# CONNECTORS.net
KiCad netlist of a schematic drawn in Altium Designer
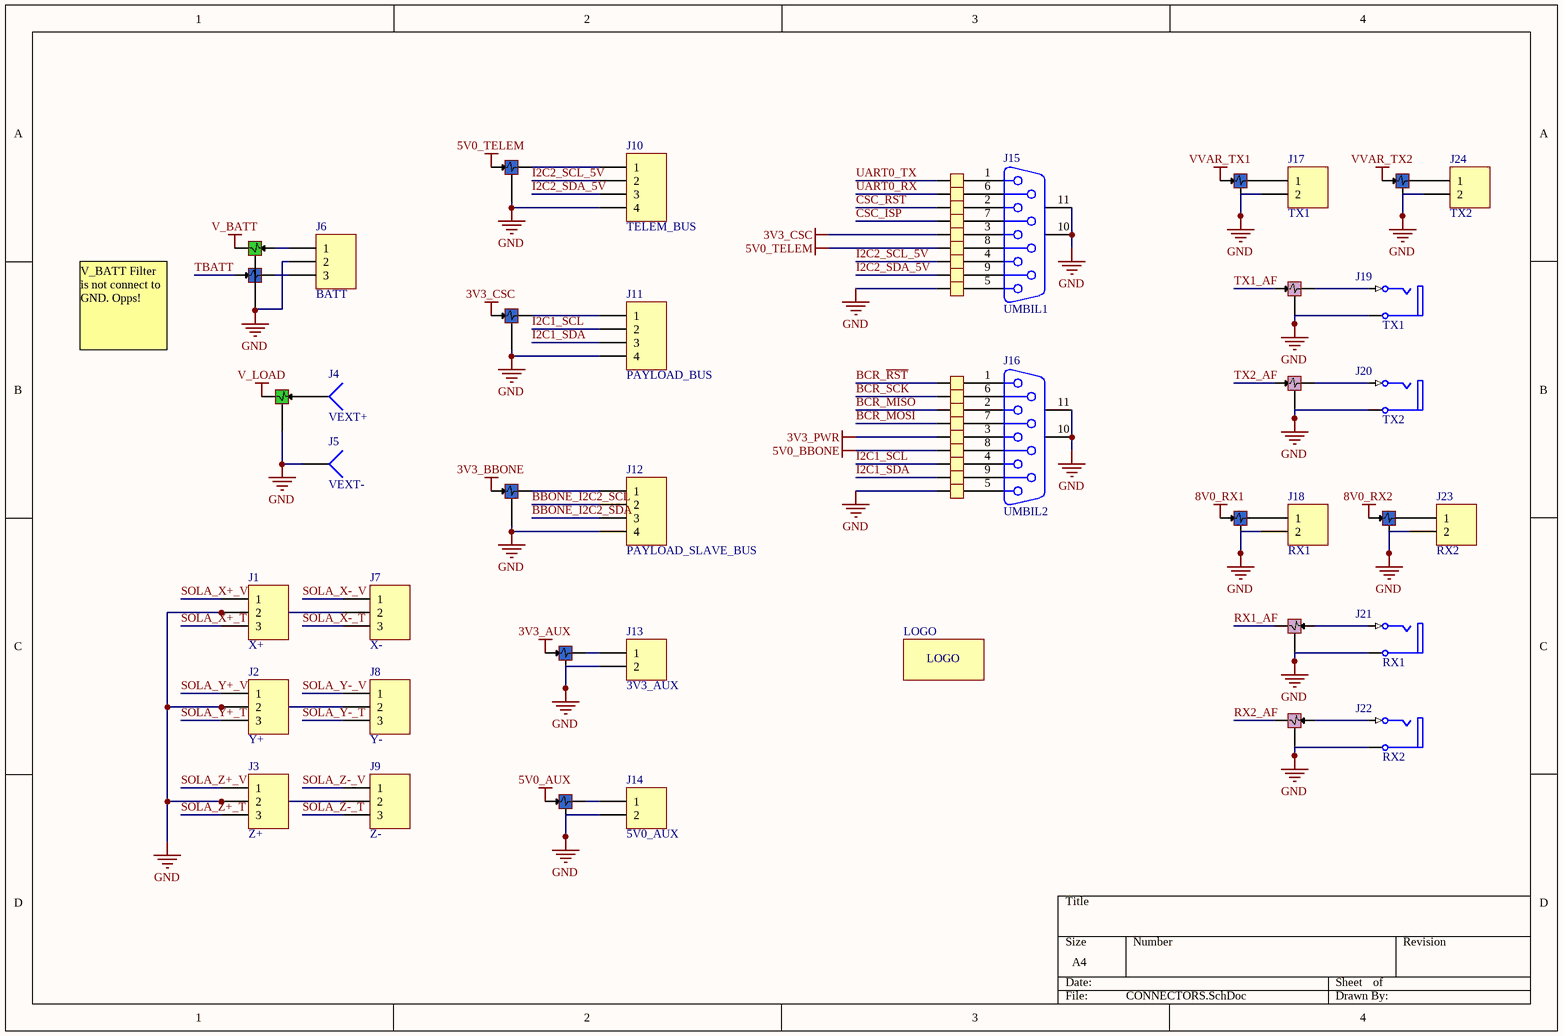
[diagram p0: CONNECTORS.SchDoc]

(export (version "E")
  (design (tool "Eeschema 10.0.6"))
  (components
    (comp (ref "F1")
      (value "FilterSola")
      (footprint "FILTERSOLA")
      (libsource (lib "FlatBoards") (part "FilterSola"))
    )
    (comp (ref "F2")
      (value "FilterPwr")
      (footprint "FILTERPWR")
      (libsource (lib "FlatBoards") (part "FilterPwr"))
    )
    (comp (ref "F3")
      (value "FilterPwr")
      (footprint "FILTERPWR")
      (libsource (lib "FlatBoards") (part "FilterPwr"))
    )
    (comp (ref "F4")
      (value "FilterPwr")
      (footprint "FILTERPWR")
      (libsource (lib "FlatBoards") (part "FilterPwr"))
    )
    (comp (ref "F5")
      (value "FilterPwr")
      (footprint "FILTERPWR")
      (libsource (lib "FlatBoards") (part "FilterPwr"))
    )
    (comp (ref "F6")
      (value "FilterPwr")
      (footprint "FILTERPWR")
      (libsource (lib "FlatBoards") (part "FilterPwr"))
    )
    (comp (ref "F7")
      (value "FilterPwr")
      (footprint "FILTERPWR")
      (libsource (lib "FlatBoards") (part "FilterPwr"))
    )
    (comp (ref "F8")
      (value "FilterPwr")
      (footprint "FILTERPWR")
      (libsource (lib "FlatBoards") (part "FilterPwr"))
    )
    (comp (ref "F9") (value "Filter") (footprint "Filter") (libsource (lib "") (part "Filter_1")))
    (comp (ref "F10") (value "Filter") (footprint "Filter") (libsource (lib "") (part "Filter_1")))
    (comp (ref "F11") (value "Filter") (footprint "Filter") (libsource (lib "FlatBoards") (part "Filter")))
    (comp (ref "F12") (value "Filter") (footprint "Filter") (libsource (lib "FlatBoards") (part "Filter")))
    (comp (ref "F13")
      (value "FilterPwr")
      (footprint "FILTERPWR")
      (libsource (lib "FlatBoards") (part "FilterPwr"))
    )
    (comp (ref "F14")
      (value "FilterPwr")
      (footprint "FILTERPWR")
      (libsource (lib "FlatBoards") (part "FilterPwr"))
    )
    (comp (ref "F98")
      (value "FilterPwr")
      (footprint "FILTERPWR")
      (libsource (lib "FlatBoards") (part "FilterPwr"))
    )
    (comp (ref "F99")
      (value "FilterSola")
      (footprint "FILTERSOLA")
      (libsource (lib "FlatBoards") (part "FilterSola"))
    )
    (comp (ref "J1")
      (value "X+")
      (footprint "SCREW3")
      (description "Header, 3-Pin")
      (fields (field (name "PUBLISHER") "Altium Limited"))
      (libsource (lib "Miscellaneous Connectors") (part "Header 3"))
    )
    (comp (ref "J2")
      (value "Y+")
      (footprint "SCREW3")
      (description "Header, 3-Pin")
      (fields (field (name "PUBLISHER") "Altium Limited"))
      (libsource (lib "Miscellaneous Connectors") (part "Header 3"))
    )
    (comp (ref "J3")
      (value "Z+")
      (footprint "SCREW3")
      (description "Header, 3-Pin")
      (fields (field (name "PUBLISHER") "Altium Limited"))
      (libsource (lib "Miscellaneous Connectors") (part "Header 3"))
    )
    (comp (ref "J4")
      (value "VEXT+")
      (footprint "4MM_BANANA")
      (description "Socket")
      (fields (field (name "PUBLISHER") "Altium Limited"))
      (libsource (lib "Miscellaneous Connectors") (part "Socket"))
    )
    (comp (ref "J5")
      (value "VEXT-")
      (footprint "4MM_BANANA")
      (description "Socket")
      (fields (field (name "PUBLISHER") "Altium Limited"))
      (libsource (lib "Miscellaneous Connectors") (part "Socket"))
    )
    (comp (ref "J6")
      (value "BATT")
      (footprint "SCREW3")
      (description "Header, 3-Pin")
      (fields (field (name "PUBLISHER") "Altium Limited"))
      (libsource (lib "Miscellaneous Connectors") (part "Header 3"))
    )
    (comp (ref "J7")
      (value "X-")
      (footprint "SCREW3")
      (description "Header, 3-Pin")
      (fields (field (name "PUBLISHER") "Altium Limited"))
      (libsource (lib "Miscellaneous Connectors") (part "Header 3"))
    )
    (comp (ref "J8")
      (value "Y-")
      (footprint "SCREW3")
      (description "Header, 3-Pin")
      (fields (field (name "PUBLISHER") "Altium Limited"))
      (libsource (lib "Miscellaneous Connectors") (part "Header 3"))
    )
    (comp (ref "J9")
      (value "Z-")
      (footprint "SCREW3")
      (description "Header, 3-Pin")
      (fields (field (name "PUBLISHER") "Altium Limited"))
      (libsource (lib "Miscellaneous Connectors") (part "Header 3"))
    )
    (comp (ref "J10")
      (value "TELEM_BUS")
      (footprint "HDR1X4")
      (description "Header, 4-Pin")
      (fields (field (name "PUBLISHER") "Altium Limited"))
      (libsource (lib "Miscellaneous Connectors") (part "Header 4"))
    )
    (comp (ref "J11")
      (value "PAYLOAD_BUS")
      (footprint "HDR1X4")
      (description "Header, 4-Pin")
      (fields (field (name "PUBLISHER") "Altium Limited"))
      (libsource (lib "Miscellaneous Connectors") (part "Header 4"))
    )
    (comp (ref "J12")
      (value "PAYLOAD_SLAVE_BUS")
      (footprint "HDR1X4")
      (description "Header, 4-Pin")
      (fields (field (name "PUBLISHER") "Altium Limited"))
      (libsource (lib "Miscellaneous Connectors") (part "Header 4"))
    )
    (comp (ref "J13")
      (value "3V3_AUX")
      (footprint "SCREW2")
      (description "Header, 2-Pin")
      (fields (field (name "PUBLISHER") "Altium Limited"))
      (libsource (lib "Miscellaneous Connectors") (part "Header 2"))
    )
    (comp (ref "J14")
      (value "5V0_AUX")
      (footprint "SCREW2")
      (description "Header, 2-Pin")
      (fields (field (name "PUBLISHER") "Altium Limited"))
      (libsource (lib "Miscellaneous Connectors") (part "Header 2"))
    )
    (comp (ref "J15")
      (value "UMBIL1")
      (footprint "D9 - temp")
      (description "Receptacle Assembly, 9 Position, Right Angle")
      (fields (field (name "PUBLISHER") "Altium Limited"))
      (libsource (lib "Miscellaneous Connectors") (part "D Connector 9"))
    )
    (comp (ref "J16")
      (value "UMBIL2")
      (footprint "D9 - temp")
      (description "Receptacle Assembly, 9 Position, Right Angle")
      (fields (field (name "PUBLISHER") "Altium Limited"))
      (libsource (lib "Miscellaneous Connectors") (part "D Connector 9"))
    )
    (comp (ref "J17")
      (value "TX1")
      (footprint "SCREW2")
      (description "Header, 2-Pin")
      (fields (field (name "PUBLISHER") "Altium Limited"))
      (libsource (lib "Miscellaneous Connectors") (part "Header 2"))
    )
    (comp (ref "J18")
      (value "RX1")
      (footprint "SCREW2")
      (description "Header, 2-Pin")
      (fields (field (name "PUBLISHER") "Altium Limited"))
      (libsource (lib "Miscellaneous Connectors") (part "Header 2"))
    )
    (comp (ref "J19")
      (value "TX1")
      (footprint "R/A RCA")
      (description "RCA Phono Jack, Right Angle, Thru-Hole, Snap-In")
      (fields (field (name "PUBLISHER") "Altium Limited"))
      (libsource (lib "Miscellaneous Connectors") (part "RCA"))
    )
    (comp (ref "J20")
      (value "TX2")
      (footprint "R/A RCA")
      (description "RCA Phono Jack, Right Angle, Thru-Hole, Snap-In")
      (fields (field (name "PUBLISHER") "Altium Limited"))
      (libsource (lib "Miscellaneous Connectors") (part "RCA"))
    )
    (comp (ref "J21")
      (value "RX1")
      (footprint "R/A RCA")
      (description "RCA Phono Jack, Right Angle, Thru-Hole, Snap-In")
      (fields (field (name "PUBLISHER") "Altium Limited"))
      (libsource (lib "Miscellaneous Connectors") (part "RCA"))
    )
    (comp (ref "J22")
      (value "RX2")
      (footprint "R/A RCA")
      (description "RCA Phono Jack, Right Angle, Thru-Hole, Snap-In")
      (fields (field (name "PUBLISHER") "Altium Limited"))
      (libsource (lib "Miscellaneous Connectors") (part "RCA"))
    )
    (comp (ref "J23")
      (value "RX2")
      (footprint "SCREW2")
      (description "Header, 2-Pin")
      (fields (field (name "PUBLISHER") "Altium Limited"))
      (libsource (lib "Miscellaneous Connectors") (part "Header 2"))
    )
    (comp (ref "J24")
      (value "TX2")
      (footprint "SCREW2")
      (description "Header, 2-Pin")
      (fields (field (name "PUBLISHER") "Altium Limited"))
      (libsource (lib "Miscellaneous Connectors") (part "Header 2"))
    )
    (comp (ref "LOGO") (value "~") (footprint "LOGO") (libsource (lib "FlatBoards") (part "LOGO")))
    (comp (ref "P185") (value "Jumper") (footprint "Jumper") (libsource (lib "FlatBoards") (part "Jumper")))
    (comp (ref "P186") (value "Jumper") (footprint "Jumper") (libsource (lib "FlatBoards") (part "Jumper")))
    (comp (ref "P187") (value "Jumper") (footprint "Jumper") (libsource (lib "FlatBoards") (part "Jumper")))
    (comp (ref "P188") (value "Jumper") (footprint "Jumper") (libsource (lib "FlatBoards") (part "Jumper")))
    (comp (ref "P189") (value "Jumper") (footprint "Jumper") (libsource (lib "FlatBoards") (part "Jumper")))
    (comp (ref "P190") (value "Jumper") (footprint "Jumper") (libsource (lib "FlatBoards") (part "Jumper")))
    (comp (ref "P191") (value "Jumper") (footprint "Jumper") (libsource (lib "FlatBoards") (part "Jumper")))
    (comp (ref "P192") (value "Jumper") (footprint "Jumper") (libsource (lib "FlatBoards") (part "Jumper")))
    (comp (ref "P193") (value "Jumper") (footprint "Jumper") (libsource (lib "FlatBoards") (part "Jumper")))
    (comp (ref "P194") (value "Jumper") (footprint "Jumper") (libsource (lib "FlatBoards") (part "Jumper")))
    (comp (ref "P195") (value "Jumper") (footprint "Jumper") (libsource (lib "FlatBoards") (part "Jumper")))
    (comp (ref "P196") (value "Jumper") (footprint "Jumper") (libsource (lib "FlatBoards") (part "Jumper")))
    (comp (ref "P197") (value "Jumper") (footprint "Jumper") (libsource (lib "FlatBoards") (part "Jumper")))
    (comp (ref "P198") (value "Jumper") (footprint "Jumper") (libsource (lib "FlatBoards") (part "Jumper")))
    (comp (ref "P199") (value "Jumper") (footprint "Jumper") (libsource (lib "FlatBoards") (part "Jumper")))
    (comp (ref "P200") (value "Jumper") (footprint "Jumper") (libsource (lib "FlatBoards") (part "Jumper")))
    (comp (ref "P201") (value "Jumper") (footprint "Jumper") (libsource (lib "FlatBoards") (part "Jumper")))
    (comp (ref "P202") (value "Jumper") (footprint "Jumper") (libsource (lib "FlatBoards") (part "Jumper")))
  )
  (nets
    (net (code "1") (name "/BBONE_I2C2_SCL") (class "Default")
      (node (ref "J12") (pin "2") (pinfunction "2_2") (pintype "passive"))
    )
    (net (code "2") (name "/BBONE_I2C2_SDA") (class "Default")
      (node (ref "J12") (pin "3") (pinfunction "3_3") (pintype "passive"))
    )
    (net (code "3") (name "/BCR_MISO") (class "Default") (node (ref "P196") (pin "1") (pintype "passive")))
    (net (code "4") (name "/BCR_MOSI") (class "Default") (node (ref "P197") (pin "1") (pintype "passive")))
    (net (code "5") (name "/BCR_SCK") (class "Default") (node (ref "P195") (pin "1") (pintype "passive")))
    (net (code "6") (name "/BCR_~{RST}") (class "Default") (node (ref "P194") (pin "1") (pintype "passive")))
    (net (code "7") (name "/CSC_ISP") (class "Default") (node (ref "P188") (pin "1") (pintype "passive")))
    (net (code "8") (name "/CSC_RST") (class "Default") (node (ref "P187") (pin "1") (pintype "passive")))
    (net (code "9") (name "/I2C1_SCL") (class "Default")
      (node (ref "J11") (pin "2") (pinfunction "2_2") (pintype "passive"))
      (node (ref "P200") (pin "1") (pintype "passive"))
    )
    (net (code "10") (name "/I2C1_SDA") (class "Default")
      (node (ref "J11") (pin "3") (pinfunction "3_3") (pintype "passive"))
      (node (ref "P201") (pin "1") (pintype "passive"))
    )
    (net (code "11") (name "/I2C2_SCL_5V") (class "Default")
      (node (ref "J10") (pin "2") (pinfunction "2_2") (pintype "passive"))
      (node (ref "P191") (pin "1") (pintype "passive"))
    )
    (net (code "12") (name "/I2C2_SDA_5V") (class "Default")
      (node (ref "J10") (pin "3") (pinfunction "3_3") (pintype "passive"))
      (node (ref "P192") (pin "1") (pintype "passive"))
    )
    (net (code "13") (name "/RX1_AF") (class "Default") (node (ref "F11") (pin "2") (pintype "passive")))
    (net (code "14") (name "/RX2_AF") (class "Default") (node (ref "F12") (pin "2") (pintype "passive")))
    (net (code "15") (name "/SOLA_X+_T") (class "Default")
      (node (ref "J1") (pin "3") (pinfunction "3_3") (pintype "passive"))
    )
    (net (code "16") (name "/SOLA_X+_V") (class "Default")
      (node (ref "J1") (pin "1") (pinfunction "1_1") (pintype "passive"))
    )
    (net (code "17") (name "/SOLA_X-_T") (class "Default")
      (node (ref "J7") (pin "3") (pinfunction "3_3") (pintype "passive"))
    )
    (net (code "18") (name "/SOLA_X-_V") (class "Default")
      (node (ref "J7") (pin "1") (pinfunction "1_1") (pintype "passive"))
    )
    (net (code "19") (name "/SOLA_Y+_T") (class "Default")
      (node (ref "J2") (pin "3") (pinfunction "3_3") (pintype "passive"))
    )
    (net (code "20") (name "/SOLA_Y+_V") (class "Default")
      (node (ref "J2") (pin "1") (pinfunction "1_1") (pintype "passive"))
    )
    (net (code "21") (name "/SOLA_Y-_T") (class "Default")
      (node (ref "J8") (pin "3") (pinfunction "3_3") (pintype "passive"))
    )
    (net (code "22") (name "/SOLA_Y-_V") (class "Default")
      (node (ref "J8") (pin "1") (pinfunction "1_1") (pintype "passive"))
    )
    (net (code "23") (name "/SOLA_Z+_T") (class "Default")
      (node (ref "J3") (pin "3") (pinfunction "3_3") (pintype "passive"))
    )
    (net (code "24") (name "/SOLA_Z+_V") (class "Default")
      (node (ref "J3") (pin "1") (pinfunction "1_1") (pintype "passive"))
    )
    (net (code "25") (name "/SOLA_Z-_T") (class "Default")
      (node (ref "J9") (pin "3") (pinfunction "3_3") (pintype "passive"))
    )
    (net (code "26") (name "/SOLA_Z-_V") (class "Default")
      (node (ref "J9") (pin "1") (pinfunction "1_1") (pintype "passive"))
    )
    (net (code "27") (name "/TBATT") (class "Default") (node (ref "F98") (pin "1") (pintype "passive")))
    (net (code "28") (name "/TX1_AF") (class "Default") (node (ref "F9") (pin "1") (pintype "passive")))
    (net (code "29") (name "/TX2_AF") (class "Default") (node (ref "F10") (pin "1") (pintype "passive")))
    (net (code "30") (name "/UART0_RX") (class "Default") (node (ref "P186") (pin "1") (pintype "passive")))
    (net (code "31") (name "/UART0_TX") (class "Default") (node (ref "P185") (pin "1") (pintype "passive")))
    (net (code "32") (name "3V3_AUX") (class "Default") (node (ref "F5") (pin "1") (pintype "passive")))
    (net (code "33") (name "3V3_BBONE") (class "Default") (node (ref "F4") (pin "1") (pintype "passive")))
    (net (code "34") (name "3V3_CSC") (class "Default")
      (node (ref "F3") (pin "1") (pintype "passive"))
      (node (ref "P189") (pin "1") (pintype "passive"))
    )
    (net (code "35") (name "3V3_PWR") (class "Default") (node (ref "P198") (pin "1") (pintype "passive")))
    (net (code "36") (name "5V0_AUX") (class "Default") (node (ref "F6") (pin "1") (pintype "passive")))
    (net (code "37") (name "5V0_BBONE") (class "Default") (node (ref "P199") (pin "1") (pintype "passive")))
    (net (code "38") (name "5V0_TELEM") (class "Default")
      (node (ref "F2") (pin "1") (pintype "passive"))
      (node (ref "P190") (pin "1") (pintype "passive"))
    )
    (net (code "39") (name "8V0_RX1") (class "Default") (node (ref "F8") (pin "1") (pintype "passive")))
    (net (code "40") (name "8V0_RX2") (class "Default") (node (ref "F13") (pin "1") (pintype "passive")))
    (net (code "41") (name "GND") (class "Default")
      (node (ref "F1") (pin "3") (pintype "passive"))
      (node (ref "F10") (pin "3") (pintype "passive"))
      (node (ref "F11") (pin "3") (pintype "passive"))
      (node (ref "F12") (pin "3") (pintype "passive"))
      (node (ref "F13") (pin "3") (pintype "passive"))
      (node (ref "F14") (pin "3") (pintype "passive"))
      (node (ref "F2") (pin "3") (pintype "passive"))
      (node (ref "F3") (pin "3") (pintype "passive"))
      (node (ref "F4") (pin "3") (pintype "passive"))
      (node (ref "F5") (pin "3") (pintype "passive"))
      (node (ref "F6") (pin "3") (pintype "passive"))
      (node (ref "F7") (pin "3") (pintype "passive"))
      (node (ref "F8") (pin "3") (pintype "passive"))
      (node (ref "F9") (pin "3") (pintype "passive"))
      (node (ref "F98") (pin "3") (pintype "passive"))
      (node (ref "J1") (pin "2") (pinfunction "2_2") (pintype "passive"))
      (node (ref "J10") (pin "4") (pinfunction "4_4") (pintype "passive"))
      (node (ref "J11") (pin "4") (pinfunction "4_4") (pintype "passive"))
      (node (ref "J12") (pin "4") (pinfunction "4_4") (pintype "passive"))
      (node (ref "J13") (pin "2") (pinfunction "2_2") (pintype "passive"))
      (node (ref "J14") (pin "2") (pinfunction "2_2") (pintype "passive"))
      (node (ref "J15") (pin "10") (pinfunction "MH1_10") (pintype "passive"))
      (node (ref "J15") (pin "11") (pinfunction "MH2_11") (pintype "passive"))
      (node (ref "J16") (pin "10") (pinfunction "MH1_10") (pintype "passive"))
      (node (ref "J16") (pin "11") (pinfunction "MH2_11") (pintype "passive"))
      (node (ref "J17") (pin "2") (pinfunction "2_2") (pintype "passive"))
      (node (ref "J18") (pin "2") (pinfunction "2_2") (pintype "passive"))
      (node (ref "J19") (pin "1A") (pinfunction "Ground_1A") (pintype "power_in"))
      (node (ref "J2") (pin "2") (pinfunction "2_2") (pintype "passive"))
      (node (ref "J20") (pin "1A") (pinfunction "Ground_1A") (pintype "power_in"))
      (node (ref "J21") (pin "1A") (pinfunction "Ground_1A") (pintype "power_in"))
      (node (ref "J22") (pin "1A") (pinfunction "Ground_1A") (pintype "power_in"))
      (node (ref "J23") (pin "2") (pinfunction "2_2") (pintype "passive"))
      (node (ref "J24") (pin "2") (pinfunction "2_2") (pintype "passive"))
      (node (ref "J3") (pin "2") (pinfunction "2_2") (pintype "passive"))
      (node (ref "J5") (pin "1") (pinfunction "1_1") (pintype "passive"))
      (node (ref "J6") (pin "2") (pinfunction "2_2") (pintype "passive"))
      (node (ref "J7") (pin "2") (pinfunction "2_2") (pintype "passive"))
      (node (ref "J8") (pin "2") (pinfunction "2_2") (pintype "passive"))
      (node (ref "J9") (pin "2") (pinfunction "2_2") (pintype "passive"))
      (node (ref "P193") (pin "1") (pintype "passive"))
      (node (ref "P202") (pin "1") (pintype "passive"))
    )
    (net (code "42") (name "Net-(F1-Pad1)") (class "Default")
      (node (ref "F1") (pin "1") (pintype "passive"))
      (node (ref "J4") (pin "1") (pinfunction "1_1") (pintype "passive"))
    )
    (net (code "43") (name "Net-(F2-Pad2)") (class "Default")
      (node (ref "F2") (pin "2") (pintype "passive"))
      (node (ref "J10") (pin "1") (pinfunction "1_1") (pintype "passive"))
    )
    (net (code "44") (name "Net-(F3-Pad2)") (class "Default")
      (node (ref "F3") (pin "2") (pintype "passive"))
      (node (ref "J11") (pin "1") (pinfunction "1_1") (pintype "passive"))
    )
    (net (code "45") (name "Net-(F4-Pad2)") (class "Default")
      (node (ref "F4") (pin "2") (pintype "passive"))
      (node (ref "J12") (pin "1") (pinfunction "1_1") (pintype "passive"))
    )
    (net (code "46") (name "Net-(F5-Pad2)") (class "Default")
      (node (ref "F5") (pin "2") (pintype "passive"))
      (node (ref "J13") (pin "1") (pinfunction "1_1") (pintype "passive"))
    )
    (net (code "47") (name "Net-(F6-Pad2)") (class "Default")
      (node (ref "F6") (pin "2") (pintype "passive"))
      (node (ref "J14") (pin "1") (pinfunction "1_1") (pintype "passive"))
    )
    (net (code "48") (name "Net-(F7-Pad2)") (class "Default")
      (node (ref "F7") (pin "2") (pintype "passive"))
      (node (ref "J17") (pin "1") (pinfunction "1_1") (pintype "passive"))
    )
    (net (code "49") (name "Net-(F8-Pad2)") (class "Default")
      (node (ref "F8") (pin "2") (pintype "passive"))
      (node (ref "J18") (pin "1") (pinfunction "1_1") (pintype "passive"))
    )
    (net (code "50") (name "Net-(F13-Pad2)") (class "Default")
      (node (ref "F13") (pin "2") (pintype "passive"))
      (node (ref "J23") (pin "1") (pinfunction "1_1") (pintype "passive"))
    )
    (net (code "51") (name "Net-(F14-Pad2)") (class "Default")
      (node (ref "F14") (pin "2") (pintype "passive"))
      (node (ref "J24") (pin "1") (pinfunction "1_1") (pintype "passive"))
    )
    (net (code "52") (name "Net-(F98-Pad2)") (class "Default")
      (node (ref "F98") (pin "2") (pintype "passive"))
      (node (ref "J6") (pin "3") (pinfunction "3_3") (pintype "passive"))
    )
    (net (code "53") (name "Net-(F99-Pad1)") (class "Default")
      (node (ref "F99") (pin "1") (pintype "passive"))
      (node (ref "J6") (pin "1") (pinfunction "1_1") (pintype "passive"))
    )
    (net (code "54") (name "Net-(J15-Pad1)") (class "Default")
      (node (ref "J15") (pin "1") (pinfunction "1_1") (pintype "passive"))
      (node (ref "P185") (pin "2") (pintype "passive"))
    )
    (net (code "55") (name "Net-(J15-Pad2)") (class "Default")
      (node (ref "J15") (pin "2") (pinfunction "2_2") (pintype "passive"))
      (node (ref "P187") (pin "2") (pintype "passive"))
    )
    (net (code "56") (name "Net-(J15-Pad3)") (class "Default")
      (node (ref "J15") (pin "3") (pinfunction "3_3") (pintype "passive"))
      (node (ref "P189") (pin "2") (pintype "passive"))
    )
    (net (code "57") (name "Net-(J15-Pad4)") (class "Default")
      (node (ref "J15") (pin "4") (pinfunction "4_4") (pintype "passive"))
      (node (ref "P191") (pin "2") (pintype "passive"))
    )
    (net (code "58") (name "Net-(J15-Pad5)") (class "Default")
      (node (ref "J15") (pin "5") (pinfunction "5_5") (pintype "passive"))
      (node (ref "P193") (pin "2") (pintype "passive"))
    )
    (net (code "59") (name "Net-(J15-Pad6)") (class "Default")
      (node (ref "J15") (pin "6") (pinfunction "6_6") (pintype "passive"))
      (node (ref "P186") (pin "2") (pintype "passive"))
    )
    (net (code "60") (name "Net-(J15-Pad7)") (class "Default")
      (node (ref "J15") (pin "7") (pinfunction "7_7") (pintype "passive"))
      (node (ref "P188") (pin "2") (pintype "passive"))
    )
    (net (code "61") (name "Net-(J15-Pad8)") (class "Default")
      (node (ref "J15") (pin "8") (pinfunction "8_8") (pintype "passive"))
      (node (ref "P190") (pin "2") (pintype "passive"))
    )
    (net (code "62") (name "Net-(J15-Pad9)") (class "Default")
      (node (ref "J15") (pin "9") (pinfunction "9_9") (pintype "passive"))
      (node (ref "P192") (pin "2") (pintype "passive"))
    )
    (net (code "63") (name "Net-(J16-Pad1)") (class "Default")
      (node (ref "J16") (pin "1") (pinfunction "1_1") (pintype "passive"))
      (node (ref "P194") (pin "2") (pintype "passive"))
    )
    (net (code "64") (name "Net-(J16-Pad2)") (class "Default")
      (node (ref "J16") (pin "2") (pinfunction "2_2") (pintype "passive"))
      (node (ref "P196") (pin "2") (pintype "passive"))
    )
    (net (code "65") (name "Net-(J16-Pad3)") (class "Default")
      (node (ref "J16") (pin "3") (pinfunction "3_3") (pintype "passive"))
      (node (ref "P198") (pin "2") (pintype "passive"))
    )
    (net (code "66") (name "Net-(J16-Pad4)") (class "Default")
      (node (ref "J16") (pin "4") (pinfunction "4_4") (pintype "passive"))
      (node (ref "P200") (pin "2") (pintype "passive"))
    )
    (net (code "67") (name "Net-(J16-Pad5)") (class "Default")
      (node (ref "J16") (pin "5") (pinfunction "5_5") (pintype "passive"))
      (node (ref "P202") (pin "2") (pintype "passive"))
    )
    (net (code "68") (name "Net-(J16-Pad6)") (class "Default")
      (node (ref "J16") (pin "6") (pinfunction "6_6") (pintype "passive"))
      (node (ref "P195") (pin "2") (pintype "passive"))
    )
    (net (code "69") (name "Net-(J16-Pad7)") (class "Default")
      (node (ref "J16") (pin "7") (pinfunction "7_7") (pintype "passive"))
      (node (ref "P197") (pin "2") (pintype "passive"))
    )
    (net (code "70") (name "Net-(J16-Pad8)") (class "Default")
      (node (ref "J16") (pin "8") (pinfunction "8_8") (pintype "passive"))
      (node (ref "P199") (pin "2") (pintype "passive"))
    )
    (net (code "71") (name "Net-(J16-Pad9)") (class "Default")
      (node (ref "J16") (pin "9") (pinfunction "9_9") (pintype "passive"))
      (node (ref "P201") (pin "2") (pintype "passive"))
    )
    (net (code "72") (name "Net-(J19-Signal)") (class "Default")
      (node (ref "F9") (pin "2") (pintype "passive"))
      (node (ref "J19") (pin "2B") (pinfunction "Signal_2B") (pintype "input"))
    )
    (net (code "73") (name "Net-(J20-Signal)") (class "Default")
      (node (ref "F10") (pin "2") (pintype "passive"))
      (node (ref "J20") (pin "2B") (pinfunction "Signal_2B") (pintype "input"))
    )
    (net (code "74") (name "Net-(J21-Signal)") (class "Default")
      (node (ref "F11") (pin "1") (pintype "passive"))
      (node (ref "J21") (pin "2B") (pinfunction "Signal_2B") (pintype "input"))
    )
    (net (code "75") (name "Net-(J22-Signal)") (class "Default")
      (node (ref "F12") (pin "1") (pintype "passive"))
      (node (ref "J22") (pin "2B") (pinfunction "Signal_2B") (pintype "input"))
    )
    (net (code "76") (name "VVAR_TX1") (class "Default") (node (ref "F7") (pin "1") (pintype "passive")))
    (net (code "77") (name "VVAR_TX2") (class "Default") (node (ref "F14") (pin "1") (pintype "passive")))
    (net (code "78") (name "V_BATT") (class "Default") (node (ref "F99") (pin "2") (pintype "passive")))
    (net (code "79") (name "V_LOAD") (class "Default") (node (ref "F1") (pin "2") (pintype "passive")))
    (net (code "80") (name "unconnected-(F99-Pad3)") (class "Default")
      (node (ref "F99") (pin "3") (pintype "passive"))
    )
  )
)
